# Switches.net
KiCad netlist of a schematic drawn in Altium Designer
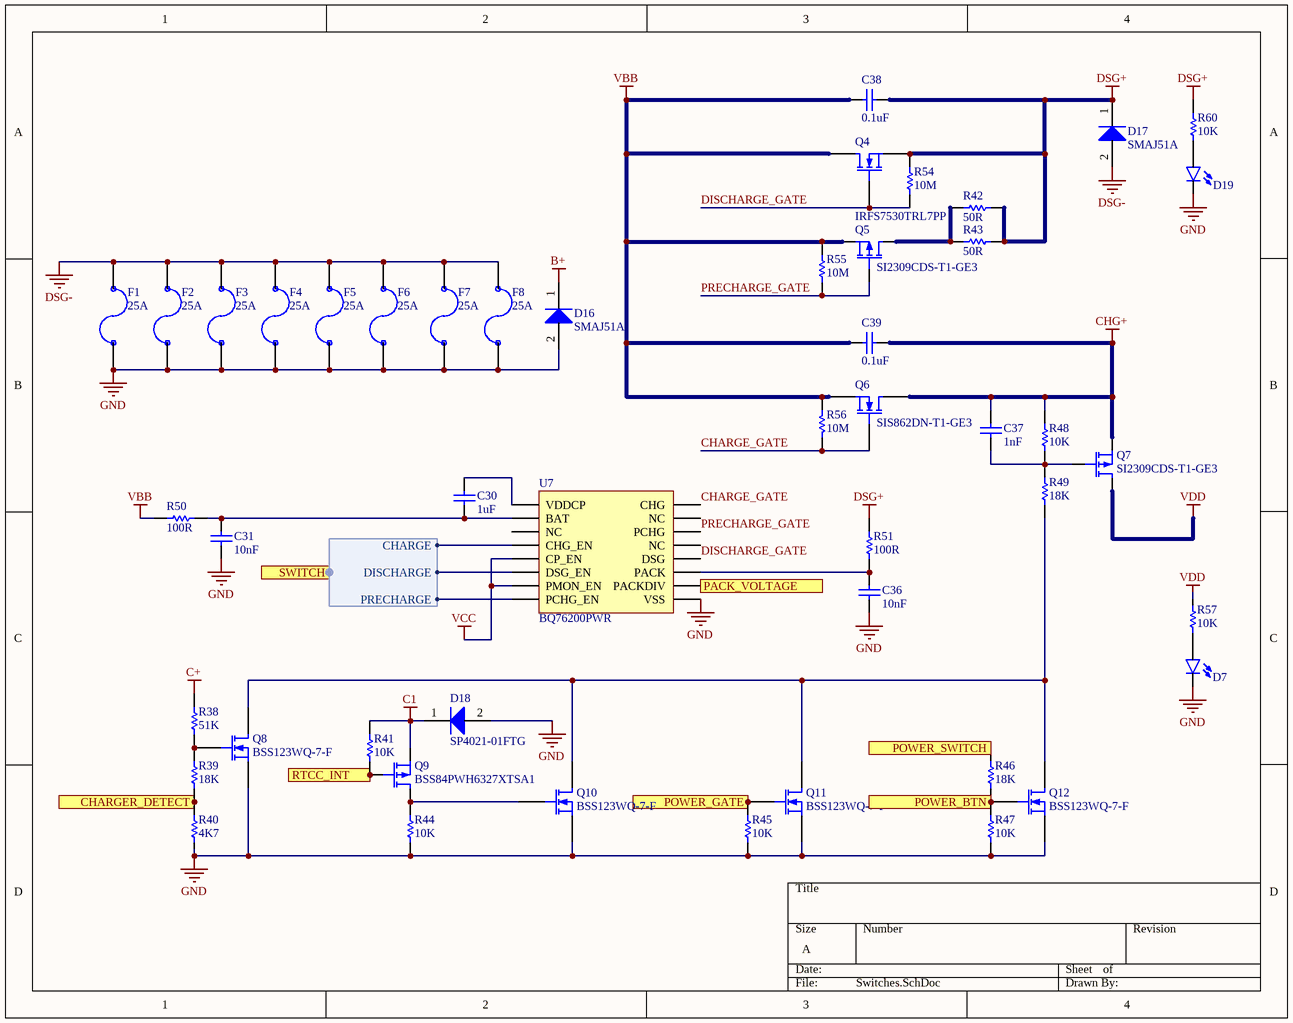
[diagram p0: Switches.SchDoc]

(export (version "E")
  (design (tool "Eeschema 10.0.6"))
  (components
    (comp (ref "C30")
      (value "1uF")
      (footprint "C0603[1608X92]")
      (description "1uF 50V 10% 0603 (1608 Metric)")
      (fields (field (name "TOLERANCE") "10%") (field (name "PARTNUMBER") "GRM188R61H105KAALD"))
      (libsource (lib "Capacitors") (part "CAP_1uF_50V_0603_10%"))
    )
    (comp (ref "C31")
      (value "10nF")
      (footprint "C0603[1608X92]")
      (description "10nF 100V 10% 0603 (1608 Metric)")
      (fields (field (name "TOLERANCE") "10%") (field (name "PARTNUMBER") "GRM188R72A103KA01D"))
      (libsource (lib "Capacitors") (part "CAP_10nF_100V_0603_10%"))
    )
    (comp (ref "C36")
      (value "10nF")
      (footprint "C0603[1608X92]")
      (description "10nF 100V 10% 0603 (1608 Metric)")
      (fields (field (name "TOLERANCE") "10%") (field (name "PARTNUMBER") "GRM188R72A103KA01D"))
      (libsource (lib "Capacitors") (part "CAP_10nF_100V_0603_10%"))
    )
    (comp (ref "C37")
      (value "1nF")
      (footprint "C0603[1608X92]")
      (description "1nF 50V 5% 0603 (1608 Metric)")
      (fields (field (name "PARTNUMBER") "GRM1885C1H102JA01D") (field (name "MANUFACTURER") "Murata"))
      (libsource (lib "Capacitors") (part "CAP_1nF_50V_0603_5%"))
    )
    (comp (ref "C38")
      (value "0.1uF")
      (footprint "C0603[1608X92]")
      (description "0.1uF 100V 10% 0603 (1608 Metric)")
      (fields (field (name "PARTNUMBER") "GRM188R72A104KA35D") (field (name "MANUFACTURER") "Murata"))
      (libsource (lib "Capacitors") (part "CAP_0.1uF_100V_0603_10%"))
    )
    (comp (ref "C39")
      (value "0.1uF")
      (footprint "C0603[1608X92]")
      (description "0.1uF 100V 10% 0603 (1608 Metric)")
      (fields (field (name "PARTNUMBER") "GRM188R72A104KA35D") (field (name "MANUFACTURER") "Murata"))
      (libsource (lib "Capacitors") (part "CAP_0.1uF_100V_0603_10%"))
    )
    (comp (ref "D7")
      (value "LED_0603_GREEN_5mA")
      (footprint "LED0603")
      (fields (field (name "PARTNUMBER") "LTST-C193TGKT-5A") (field (name "MANUFACTURER") "Lite-On Inc."))
      (libsource (lib "LEDs") (part "LED_0603_GREEN_5mA"))
    )
    (comp (ref "D16")
      (value "SMAJ51A")
      (footprint "DO-214AC")
      (fields (field (name "PARTNUMBER") "SMAJ51A-E3/61") (field (name "MANUFACTURER") "Vishay"))
      (libsource (lib "Diodes") (part "SMAJ51A-E3/61"))
    )
    (comp (ref "D17")
      (value "SMAJ51A")
      (footprint "DO-214AC")
      (fields (field (name "PARTNUMBER") "SMAJ51A-E3/61") (field (name "MANUFACTURER") "Vishay"))
      (libsource (lib "Diodes") (part "SMAJ51A-E3/61"))
    )
    (comp (ref "D18")
      (value "SP4021-01FTG")
      (footprint "SOD-323")
      (fields (field (name "MANUFACTURER") "Littelfuse"))
      (libsource (lib "Diodes-TVS") (part "SP4021-01FTG"))
    )
    (comp (ref "D19")
      (value "LED_0603_GREEN_5mA")
      (footprint "LED0603")
      (fields (field (name "PARTNUMBER") "LTST-C193TGKT-5A") (field (name "MANUFACTURER") "Lite-On Inc."))
      (libsource (lib "LEDs") (part "LED_0603_GREEN_5mA"))
    )
    (comp (ref "F1")
      (value "FUSE 1206")
      (footprint "1206_FUSE")
      (description "Surface Mount Fuses UST 1206 FUSE 25A F")
      (fields
        (field (name "PARTNUMBER") "3413.0332.22")
        (field (name "MANUFACTURER") "Schurter")
        (field (name "CURRENT") "25A")
      )
      (libsource (lib "Components") (part "FUSE 1206"))
    )
    (comp (ref "F2")
      (value "FUSE 1206")
      (footprint "1206_FUSE")
      (description "Surface Mount Fuses UST 1206 FUSE 25A F")
      (fields
        (field (name "PARTNUMBER") "3413.0332.22")
        (field (name "MANUFACTURER") "Schurter")
        (field (name "CURRENT") "25A")
      )
      (libsource (lib "Components") (part "FUSE 1206"))
    )
    (comp (ref "F3")
      (value "FUSE 1206")
      (footprint "1206_FUSE")
      (description "Surface Mount Fuses UST 1206 FUSE 25A F")
      (fields
        (field (name "PARTNUMBER") "3413.0332.22")
        (field (name "MANUFACTURER") "Schurter")
        (field (name "CURRENT") "25A")
      )
      (libsource (lib "Components") (part "FUSE 1206"))
    )
    (comp (ref "F4")
      (value "FUSE 1206")
      (footprint "1206_FUSE")
      (description "Surface Mount Fuses UST 1206 FUSE 25A F")
      (fields
        (field (name "PARTNUMBER") "3413.0332.22")
        (field (name "MANUFACTURER") "Schurter")
        (field (name "CURRENT") "25A")
      )
      (libsource (lib "Components") (part "FUSE 1206"))
    )
    (comp (ref "F5")
      (value "FUSE 1206")
      (footprint "1206_FUSE")
      (description "Surface Mount Fuses UST 1206 FUSE 25A F")
      (fields
        (field (name "PARTNUMBER") "3413.0332.22")
        (field (name "MANUFACTURER") "Schurter")
        (field (name "CURRENT") "25A")
      )
      (libsource (lib "Components") (part "FUSE 1206"))
    )
    (comp (ref "F6")
      (value "FUSE 1206")
      (footprint "1206_FUSE")
      (description "Surface Mount Fuses UST 1206 FUSE 25A F")
      (fields
        (field (name "PARTNUMBER") "3413.0332.22")
        (field (name "MANUFACTURER") "Schurter")
        (field (name "CURRENT") "25A")
      )
      (libsource (lib "Components") (part "FUSE 1206"))
    )
    (comp (ref "F7")
      (value "FUSE 1206")
      (footprint "1206_FUSE")
      (description "Surface Mount Fuses UST 1206 FUSE 25A F")
      (fields
        (field (name "PARTNUMBER") "3413.0332.22")
        (field (name "MANUFACTURER") "Schurter")
        (field (name "CURRENT") "25A")
      )
      (libsource (lib "Components") (part "FUSE 1206"))
    )
    (comp (ref "F8")
      (value "FUSE 1206")
      (footprint "1206_FUSE")
      (description "Surface Mount Fuses UST 1206 FUSE 25A F")
      (fields
        (field (name "PARTNUMBER") "3413.0332.22")
        (field (name "MANUFACTURER") "Schurter")
        (field (name "CURRENT") "25A")
      )
      (libsource (lib "Components") (part "FUSE 1206"))
    )
    (comp (ref "Q4")
      (value "IRFS7530TRL7PP")
      (footprint "D2PAK-7")
      (description "N-Channel MOSFET")
      (fields (field (name "MANUFACTURER") "Infineon") (field (name "PUBLISHER") "Altium Limited"))
      (libsource (lib "MOSFETs") (part "IRFS7530TRL7PP"))
    )
    (comp (ref "Q5")
      (value "SI2309CDS-T1-GE3")
      (footprint "SOT23-3")
      (description "P-Channel MOSFET")
      (fields (field (name "MANUFACTURER") "Vishay"))
      (libsource (lib "MOSFETs") (part "SI2309CDS-T1-GE3"))
    )
    (comp (ref "Q6")
      (value "SIS862DN-T1-GE3")
      (footprint "PowerPak-1212-8")
      (description "N-Channel MOSFET")
      (fields (field (name "MANUFACTURER") "Vishay"))
      (libsource (lib "MOSFETs") (part "SIS862DN-T1-GE3"))
    )
    (comp (ref "Q7")
      (value "SI2309CDS-T1-GE3")
      (footprint "SOT23-3")
      (description "P-Channel MOSFET")
      (fields (field (name "MANUFACTURER") "Vishay"))
      (libsource (lib "MOSFETs") (part "SI2309CDS-T1-GE3"))
    )
    (comp (ref "Q8")
      (value "BSS123WQ-7-F")
      (footprint "SOT323-3")
      (description "N-Channel MOSFET")
      (fields (field (name "MANUFACTURER") "Diodes Incorporated"))
      (libsource (lib "MOSFETs") (part "BSS123WQ-7-F"))
    )
    (comp (ref "Q9")
      (value "BSS84PWH6327XTSA1")
      (footprint "SOT323-3")
      (description "P-Channel MOSFET")
      (fields (field (name "MANUFACTURER") "Infineon"))
      (libsource (lib "MOSFETs") (part "BSS84PW H6327"))
    )
    (comp (ref "Q10")
      (value "BSS123WQ-7-F")
      (footprint "SOT323-3")
      (description "N-Channel MOSFET")
      (fields (field (name "MANUFACTURER") "Diodes Incorporated"))
      (libsource (lib "MOSFETs") (part "BSS123WQ-7-F"))
    )
    (comp (ref "Q11")
      (value "BSS123WQ-7-F")
      (footprint "SOT323-3")
      (description "N-Channel MOSFET")
      (fields (field (name "MANUFACTURER") "Diodes Incorporated"))
      (libsource (lib "MOSFETs") (part "BSS123WQ-7-F"))
    )
    (comp (ref "Q12")
      (value "BSS123WQ-7-F")
      (footprint "SOT323-3")
      (description "N-Channel MOSFET")
      (fields (field (name "MANUFACTURER") "Diodes Incorporated"))
      (libsource (lib "MOSFETs") (part "BSS123WQ-7-F"))
    )
    (comp (ref "R38")
      (value "51K")
      (footprint "R0603[1608]")
      (description "51K 0.25W 1% 0603 (1005 Metric)")
      (fields (field (name "POWER") "0.25W") (field (name "TOLERANCE") "1%"))
      (libsource (lib "Resistors") (part "RES_51K_0603_1%"))
    )
    (comp (ref "R39")
      (value "18K")
      (footprint "R0603[1608]")
      (description "18K 0.25W 1% 0603 (1005 Metric)")
      (fields (field (name "TOLERANCE") "1%") (field (name "POWER") "0.25W"))
      (libsource (lib "Resistors") (part "RES_18K_0603_1%"))
    )
    (comp (ref "R40")
      (value "4K7")
      (footprint "R0603[1608]")
      (description "4K7 0.25W 1% 0603 (1005 Metric)")
      (fields (field (name "TOLERANCE") "1%") (field (name "POWER") "0.25W"))
      (libsource (lib "Resistors") (part "RES_4K7_0603_1%"))
    )
    (comp (ref "R41")
      (value "10K")
      (footprint "R0603[1608]")
      (description "10K 0.25W 1% 0603 (1005 Metric)")
      (fields (field (name "MANUFACTURER") "Vishay") (field (name "PARTNUMBER") "RCS060310K0FKEA"))
      (libsource (lib "Resistors") (part "RES_10K_0603_1%"))
    )
    (comp (ref "R42")
      (value "50R")
      (footprint "R1206[3216]")
      (description "50R 2.4W 2% 1206 (3216 Metric)")
      (fields (field (name "TOLERANCE") "2%") (field (name "POWER") "2.4W"))
      (libsource (lib "Resistors") (part "RES_50R_1206_2%"))
    )
    (comp (ref "R43")
      (value "50R")
      (footprint "R1206[3216]")
      (description "50R 2.4W 2% 1206 (3216 Metric)")
      (fields (field (name "TOLERANCE") "2%") (field (name "POWER") "2.4W"))
      (libsource (lib "Resistors") (part "RES_50R_1206_2%"))
    )
    (comp (ref "R44")
      (value "10K")
      (footprint "R0603[1608]")
      (description "10K 0.25W 1% 0603 (1005 Metric)")
      (fields (field (name "MANUFACTURER") "Vishay") (field (name "PARTNUMBER") "RCS060310K0FKEA"))
      (libsource (lib "Resistors") (part "RES_10K_0603_1%"))
    )
    (comp (ref "R45")
      (value "10K")
      (footprint "R0603[1608]")
      (description "10K 0.25W 1% 0603 (1005 Metric)")
      (fields (field (name "MANUFACTURER") "Vishay") (field (name "PARTNUMBER") "RCS060310K0FKEA"))
      (libsource (lib "Resistors") (part "RES_10K_0603_1%"))
    )
    (comp (ref "R46")
      (value "18K")
      (footprint "R0603[1608]")
      (description "18K 0.25W 1% 0603 (1005 Metric)")
      (fields (field (name "TOLERANCE") "1%") (field (name "POWER") "0.25W"))
      (libsource (lib "Resistors") (part "RES_18K_0603_1%"))
    )
    (comp (ref "R47")
      (value "10K")
      (footprint "R0603[1608]")
      (description "10K 0.25W 1% 0603 (1005 Metric)")
      (fields (field (name "POWER") "0.25W") (field (name "TOLERANCE") "1%"))
      (libsource (lib "Resistors") (part "RES_10K_0603_1%"))
    )
    (comp (ref "R48")
      (value "10K")
      (footprint "R0603[1608]")
      (description "10K 0.25W 1% 0603 (1005 Metric)")
      (fields (field (name "TOLERANCE") "1%") (field (name "POWER") "0.25W"))
      (libsource (lib "Resistors") (part "RES_10K_0603_1%"))
    )
    (comp (ref "R49")
      (value "18K")
      (footprint "R0603[1608]")
      (description "18K 0.25W 1% 0603 (1005 Metric)")
      (fields (field (name "POWER") "0.25W") (field (name "TOLERANCE") "1%"))
      (libsource (lib "Resistors") (part "RES_18K_0603_1%"))
    )
    (comp (ref "R50")
      (value "100R")
      (footprint "R0603[1608]")
      (description "100R 0.25W 1% 0603 (1005 Metric)")
      (fields (field (name "POWER") "0.25W") (field (name "TOLERANCE") "1%"))
      (libsource (lib "Resistors") (part "RES_100R_0603_1%"))
    )
    (comp (ref "R51")
      (value "100R")
      (footprint "R0603[1608]")
      (description "100R 0.25W 1% 0603 (1005 Metric)")
      (fields (field (name "POWER") "0.25W") (field (name "TOLERANCE") "1%"))
      (libsource (lib "Resistors") (part "RES_100R_0603_1%"))
    )
    (comp (ref "R54")
      (value "10M")
      (footprint "R0603[1608]")
      (description "10M 0.25W 1% 0603 (1005 Metric)")
      (fields (field (name "MANUFACTURER") "Vishay / Dale") (field (name "TOLERANCE") "1%"))
      (libsource (lib "Resistors") (part "RES_10M_0603_1%"))
    )
    (comp (ref "R55")
      (value "10M")
      (footprint "R0603[1608]")
      (description "10M 0.25W 1% 0603 (1005 Metric)")
      (fields (field (name "MANUFACTURER") "Vishay / Dale") (field (name "TOLERANCE") "1%"))
      (libsource (lib "Resistors") (part "RES_10M_0603_1%"))
    )
    (comp (ref "R56")
      (value "10M")
      (footprint "R0603[1608]")
      (description "10M 0.25W 1% 0603 (1005 Metric)")
      (fields (field (name "MANUFACTURER") "Vishay / Dale") (field (name "TOLERANCE") "1%"))
      (libsource (lib "Resistors") (part "RES_10M_0603_1%"))
    )
    (comp (ref "R57")
      (value "10K")
      (footprint "R0603[1608]")
      (description "10K 0.25W 1% 0603 (1005 Metric)")
      (fields (field (name "TOLERANCE") "1%") (field (name "POWER") "0.25W"))
      (libsource (lib "Resistors") (part "RES_10K_0603_1%"))
    )
    (comp (ref "R60")
      (value "10K")
      (footprint "R0603[1608]")
      (description "10K 0.25W 1% 0603 (1005 Metric)")
      (fields (field (name "TOLERANCE") "1%") (field (name "POWER") "0.25W"))
      (libsource (lib "Resistors") (part "RES_10K_0603_1%"))
    )
    (comp (ref "U7")
      (value "BQ76200PWR")
      (footprint "TSSOP-16")
      (description "Battery Management Fast high side NCH drive")
      (fields (field (name "MANUFACTURER") "Texas Instruments"))
      (libsource (lib "ICs") (part "BQ76200PWR"))
    )
  )
  (nets
    (net (code "2") (name "/CHARGE") (class "Default")
      (node (ref "U7") (pin "4") (pinfunction "CHG_EN_4") (pintype "passive"))
    )
    (net (code "3") (name "/CHARGER_DETECT") (class "Default")
      (node (ref "R39") (pin "1") (pinfunction "1_1") (pintype "passive"))
      (node (ref "R40") (pin "2") (pinfunction "2_2") (pintype "passive"))
    )
    (net (code "4") (name "/CHARGE_GATE") (class "Default")
      (node (ref "Q6") (pin "2") (pinfunction "G_2") (pintype "passive"))
      (node (ref "R56") (pin "1") (pinfunction "1_1") (pintype "passive"))
      (node (ref "U7") (pin "16") (pinfunction "CHG_16") (pintype "passive"))
    )
    (net (code "5") (name "/DISCHARGE") (class "Default")
      (node (ref "U7") (pin "6") (pinfunction "DSG_EN_6") (pintype "passive"))
    )
    (net (code "6") (name "/DISCHARGE_GATE") (class "Default")
      (node (ref "Q4") (pin "1") (pinfunction "G_1") (pintype "passive"))
      (node (ref "R54") (pin "1") (pinfunction "1_1") (pintype "passive"))
      (node (ref "U7") (pin "12") (pinfunction "DSG_12") (pintype "passive"))
    )
    (net (code "7") (name "/PACK_VOLTAGE") (class "Default")
      (node (ref "U7") (pin "10") (pinfunction "PACKDIV_10") (pintype "passive"))
    )
    (net (code "8") (name "/POWER_BTN") (class "Default")
      (node (ref "Q12") (pin "1") (pinfunction "G_1") (pintype "passive"))
      (node (ref "R46") (pin "1") (pinfunction "1_1") (pintype "passive"))
      (node (ref "R47") (pin "2") (pinfunction "2_2") (pintype "passive"))
    )
    (net (code "9") (name "/POWER_GATE") (class "Default")
      (node (ref "Q11") (pin "1") (pinfunction "G_1") (pintype "passive"))
      (node (ref "R45") (pin "2") (pinfunction "2_2") (pintype "passive"))
    )
    (net (code "10") (name "/POWER_SWITCH") (class "Default")
      (node (ref "R46") (pin "2") (pinfunction "2_2") (pintype "passive"))
    )
    (net (code "11") (name "/PRECHARGE") (class "Default")
      (node (ref "U7") (pin "8") (pinfunction "PCHG_EN_8") (pintype "passive"))
    )
    (net (code "12") (name "/PRECHARGE_GATE") (class "Default")
      (node (ref "Q5") (pin "1") (pinfunction "G_1") (pintype "passive"))
      (node (ref "R55") (pin "1") (pinfunction "1_1") (pintype "passive"))
      (node (ref "U7") (pin "14") (pinfunction "PCHG_14") (pintype "passive"))
    )
    (net (code "13") (name "/RTCC_INT") (class "Default")
      (node (ref "Q9") (pin "1") (pinfunction "G_1") (pintype "passive"))
      (node (ref "R41") (pin "1") (pinfunction "1_1") (pintype "passive"))
    )
    (net (code "15") (name "B+") (class "Default")
      (node (ref "D16") (pin "1") (pinfunction "K_1") (pintype "passive"))
    )
    (net (code "16") (name "C+") (class "Default")
      (node (ref "R38") (pin "2") (pinfunction "2_2") (pintype "passive"))
    )
    (net (code "17") (name "C1") (class "Default")
      (node (ref "D18") (pin "1") (pinfunction "K_1") (pintype "passive"))
      (node (ref "Q9") (pin "2") (pinfunction "S_2") (pintype "passive"))
      (node (ref "R41") (pin "2") (pinfunction "2_2") (pintype "passive"))
    )
    (net (code "18") (name "CHG+") (class "Default")
      (node (ref "C37") (pin "2") (pinfunction "2_2") (pintype "passive"))
      (node (ref "C39") (pin "2") (pinfunction "2_2") (pintype "passive"))
      (node (ref "Q6") (pin "3") (pinfunction "D_3") (pintype "passive"))
      (node (ref "Q7") (pin "3") (pinfunction "S_3") (pintype "passive"))
      (node (ref "R48") (pin "2") (pinfunction "2_2") (pintype "passive"))
    )
    (net (code "19") (name "DSG+") (class "Default")
      (node (ref "C38") (pin "2") (pinfunction "2_2") (pintype "passive"))
      (node (ref "D17") (pin "1") (pinfunction "K_1") (pintype "passive"))
      (node (ref "Q4") (pin "2") (pinfunction "S_2") (pintype "passive"))
      (node (ref "R42") (pin "2") (pinfunction "2_2") (pintype "passive"))
      (node (ref "R43") (pin "2") (pinfunction "2_2") (pintype "passive"))
      (node (ref "R51") (pin "2") (pinfunction "2_2") (pintype "passive"))
      (node (ref "R54") (pin "2") (pinfunction "2_2") (pintype "passive"))
      (node (ref "R60") (pin "2") (pinfunction "2_2") (pintype "passive"))
    )
    (net (code "20") (name "DSG-") (class "Default")
      (node (ref "D17") (pin "2") (pinfunction "A_2") (pintype "passive"))
      (node (ref "F1") (pin "1") (pinfunction "1_1") (pintype "passive"))
      (node (ref "F2") (pin "1") (pinfunction "1_1") (pintype "passive"))
      (node (ref "F3") (pin "1") (pinfunction "1_1") (pintype "passive"))
      (node (ref "F4") (pin "1") (pinfunction "1_1") (pintype "passive"))
      (node (ref "F5") (pin "1") (pinfunction "1_1") (pintype "passive"))
      (node (ref "F6") (pin "1") (pinfunction "1_1") (pintype "passive"))
      (node (ref "F7") (pin "1") (pinfunction "1_1") (pintype "passive"))
      (node (ref "F8") (pin "1") (pinfunction "1_1") (pintype "passive"))
    )
    (net (code "21") (name "GND") (class "Default")
      (node (ref "C31") (pin "1") (pinfunction "1_1") (pintype "passive"))
      (node (ref "C36") (pin "1") (pinfunction "1_1") (pintype "passive"))
      (node (ref "D16") (pin "2") (pinfunction "A_2") (pintype "passive"))
      (node (ref "D18") (pin "2") (pinfunction "A_2") (pintype "passive"))
      (node (ref "D19") (pin "C") (pinfunction "C_C") (pintype "passive"))
      (node (ref "D7") (pin "C") (pinfunction "C_C") (pintype "passive"))
      (node (ref "F1") (pin "2") (pinfunction "2_2") (pintype "passive"))
      (node (ref "F2") (pin "2") (pinfunction "2_2") (pintype "passive"))
      (node (ref "F3") (pin "2") (pinfunction "2_2") (pintype "passive"))
      (node (ref "F4") (pin "2") (pinfunction "2_2") (pintype "passive"))
      (node (ref "F5") (pin "2") (pinfunction "2_2") (pintype "passive"))
      (node (ref "F6") (pin "2") (pinfunction "2_2") (pintype "passive"))
      (node (ref "F7") (pin "2") (pinfunction "2_2") (pintype "passive"))
      (node (ref "F8") (pin "2") (pinfunction "2_2") (pintype "passive"))
      (node (ref "Q10") (pin "2") (pinfunction "S_2") (pintype "passive"))
      (node (ref "Q11") (pin "2") (pinfunction "S_2") (pintype "passive"))
      (node (ref "Q12") (pin "2") (pinfunction "S_2") (pintype "passive"))
      (node (ref "Q8") (pin "2") (pinfunction "S_2") (pintype "passive"))
      (node (ref "R40") (pin "1") (pinfunction "1_1") (pintype "passive"))
      (node (ref "R44") (pin "1") (pinfunction "1_1") (pintype "passive"))
      (node (ref "R45") (pin "1") (pinfunction "1_1") (pintype "passive"))
      (node (ref "R47") (pin "1") (pinfunction "1_1") (pintype "passive"))
      (node (ref "U7") (pin "9") (pinfunction "VSS_9") (pintype "passive"))
    )
    (net (code "22") (name "Net-(D7-PadA)") (class "Default")
      (node (ref "D7") (pin "A") (pinfunction "A_A") (pintype "passive"))
      (node (ref "R57") (pin "1") (pinfunction "1_1") (pintype "passive"))
    )
    (net (code "23") (name "Net-(D19-PadA)") (class "Default")
      (node (ref "D19") (pin "A") (pinfunction "A_A") (pintype "passive"))
      (node (ref "R60") (pin "1") (pinfunction "1_1") (pintype "passive"))
    )
    (net (code "24") (name "Net-(Q5-D)") (class "Default")
      (node (ref "Q5") (pin "2") (pinfunction "D_2") (pintype "passive"))
      (node (ref "R42") (pin "1") (pinfunction "1_1") (pintype "passive"))
      (node (ref "R43") (pin "1") (pinfunction "1_1") (pintype "passive"))
    )
    (net (code "25") (name "Net-(Q7-G)") (class "Default")
      (node (ref "C37") (pin "1") (pinfunction "1_1") (pintype "passive"))
      (node (ref "Q7") (pin "1") (pinfunction "G_1") (pintype "passive"))
      (node (ref "R48") (pin "1") (pinfunction "1_1") (pintype "passive"))
      (node (ref "R49") (pin "2") (pinfunction "2_2") (pintype "passive"))
    )
    (net (code "26") (name "Net-(Q8-G)") (class "Default")
      (node (ref "Q8") (pin "1") (pinfunction "G_1") (pintype "passive"))
      (node (ref "R38") (pin "1") (pinfunction "1_1") (pintype "passive"))
      (node (ref "R39") (pin "2") (pinfunction "2_2") (pintype "passive"))
    )
    (net (code "27") (name "Net-(Q10-D)") (class "Default")
      (node (ref "Q10") (pin "3") (pinfunction "D_3") (pintype "passive"))
      (node (ref "Q11") (pin "3") (pinfunction "D_3") (pintype "passive"))
      (node (ref "Q12") (pin "3") (pinfunction "D_3") (pintype "passive"))
      (node (ref "Q8") (pin "3") (pinfunction "D_3") (pintype "passive"))
      (node (ref "R49") (pin "1") (pinfunction "1_1") (pintype "passive"))
    )
    (net (code "28") (name "Net-(Q10-G)") (class "Default")
      (node (ref "Q10") (pin "1") (pinfunction "G_1") (pintype "passive"))
      (node (ref "Q9") (pin "3") (pinfunction "D_3") (pintype "passive"))
      (node (ref "R44") (pin "2") (pinfunction "2_2") (pintype "passive"))
    )
    (net (code "29") (name "Net-(U7-BAT)") (class "Default")
      (node (ref "C30") (pin "1") (pinfunction "1_1") (pintype "passive"))
      (node (ref "C31") (pin "2") (pinfunction "2_2") (pintype "passive"))
      (node (ref "R50") (pin "2") (pinfunction "2_2") (pintype "passive"))
      (node (ref "U7") (pin "2") (pinfunction "BAT_2") (pintype "passive"))
    )
    (net (code "30") (name "Net-(U7-PACK)") (class "Default")
      (node (ref "C36") (pin "2") (pinfunction "2_2") (pintype "passive"))
      (node (ref "R51") (pin "1") (pinfunction "1_1") (pintype "passive"))
      (node (ref "U7") (pin "11") (pinfunction "PACK_11") (pintype "passive"))
    )
    (net (code "31") (name "Net-(U7-VDDCP)") (class "Default")
      (node (ref "C30") (pin "2") (pinfunction "2_2") (pintype "passive"))
      (node (ref "U7") (pin "1") (pinfunction "VDDCP_1") (pintype "passive"))
    )
    (net (code "32") (name "VBB") (class "Default")
      (node (ref "C38") (pin "1") (pinfunction "1_1") (pintype "passive"))
      (node (ref "C39") (pin "1") (pinfunction "1_1") (pintype "passive"))
      (node (ref "Q4") (pin "3") (pinfunction "D_3") (pintype "passive"))
      (node (ref "Q5") (pin "3") (pinfunction "S_3") (pintype "passive"))
      (node (ref "Q6") (pin "1") (pinfunction "S_1") (pintype "passive"))
      (node (ref "R50") (pin "1") (pinfunction "1_1") (pintype "passive"))
      (node (ref "R55") (pin "2") (pinfunction "2_2") (pintype "passive"))
      (node (ref "R56") (pin "2") (pinfunction "2_2") (pintype "passive"))
    )
    (net (code "33") (name "VCC") (class "Default")
      (node (ref "U7") (pin "5") (pinfunction "CP_EN_5") (pintype "passive"))
      (node (ref "U7") (pin "7") (pinfunction "PMON_EN_7") (pintype "passive"))
    )
    (net (code "34") (name "VDD") (class "Default")
      (node (ref "Q7") (pin "2") (pinfunction "D_2") (pintype "passive"))
      (node (ref "R57") (pin "2") (pinfunction "2_2") (pintype "passive"))
    )
    (net (code "35") (name "unconnected-(U7-NC-Pad3)") (class "Default")
      (node (ref "U7") (pin "3") (pinfunction "NC_3") (pintype "passive"))
    )
    (net (code "36") (name "unconnected-(U7-NC-Pad13)") (class "Default")
      (node (ref "U7") (pin "13") (pinfunction "NC_13") (pintype "passive"))
    )
    (net (code "37") (name "unconnected-(U7-NC-Pad15)") (class "Default")
      (node (ref "U7") (pin "15") (pinfunction "NC_15") (pintype "passive"))
    )
  )
)
